# ESC_A.net
KiCad netlist of a schematic drawn in Altium Designer
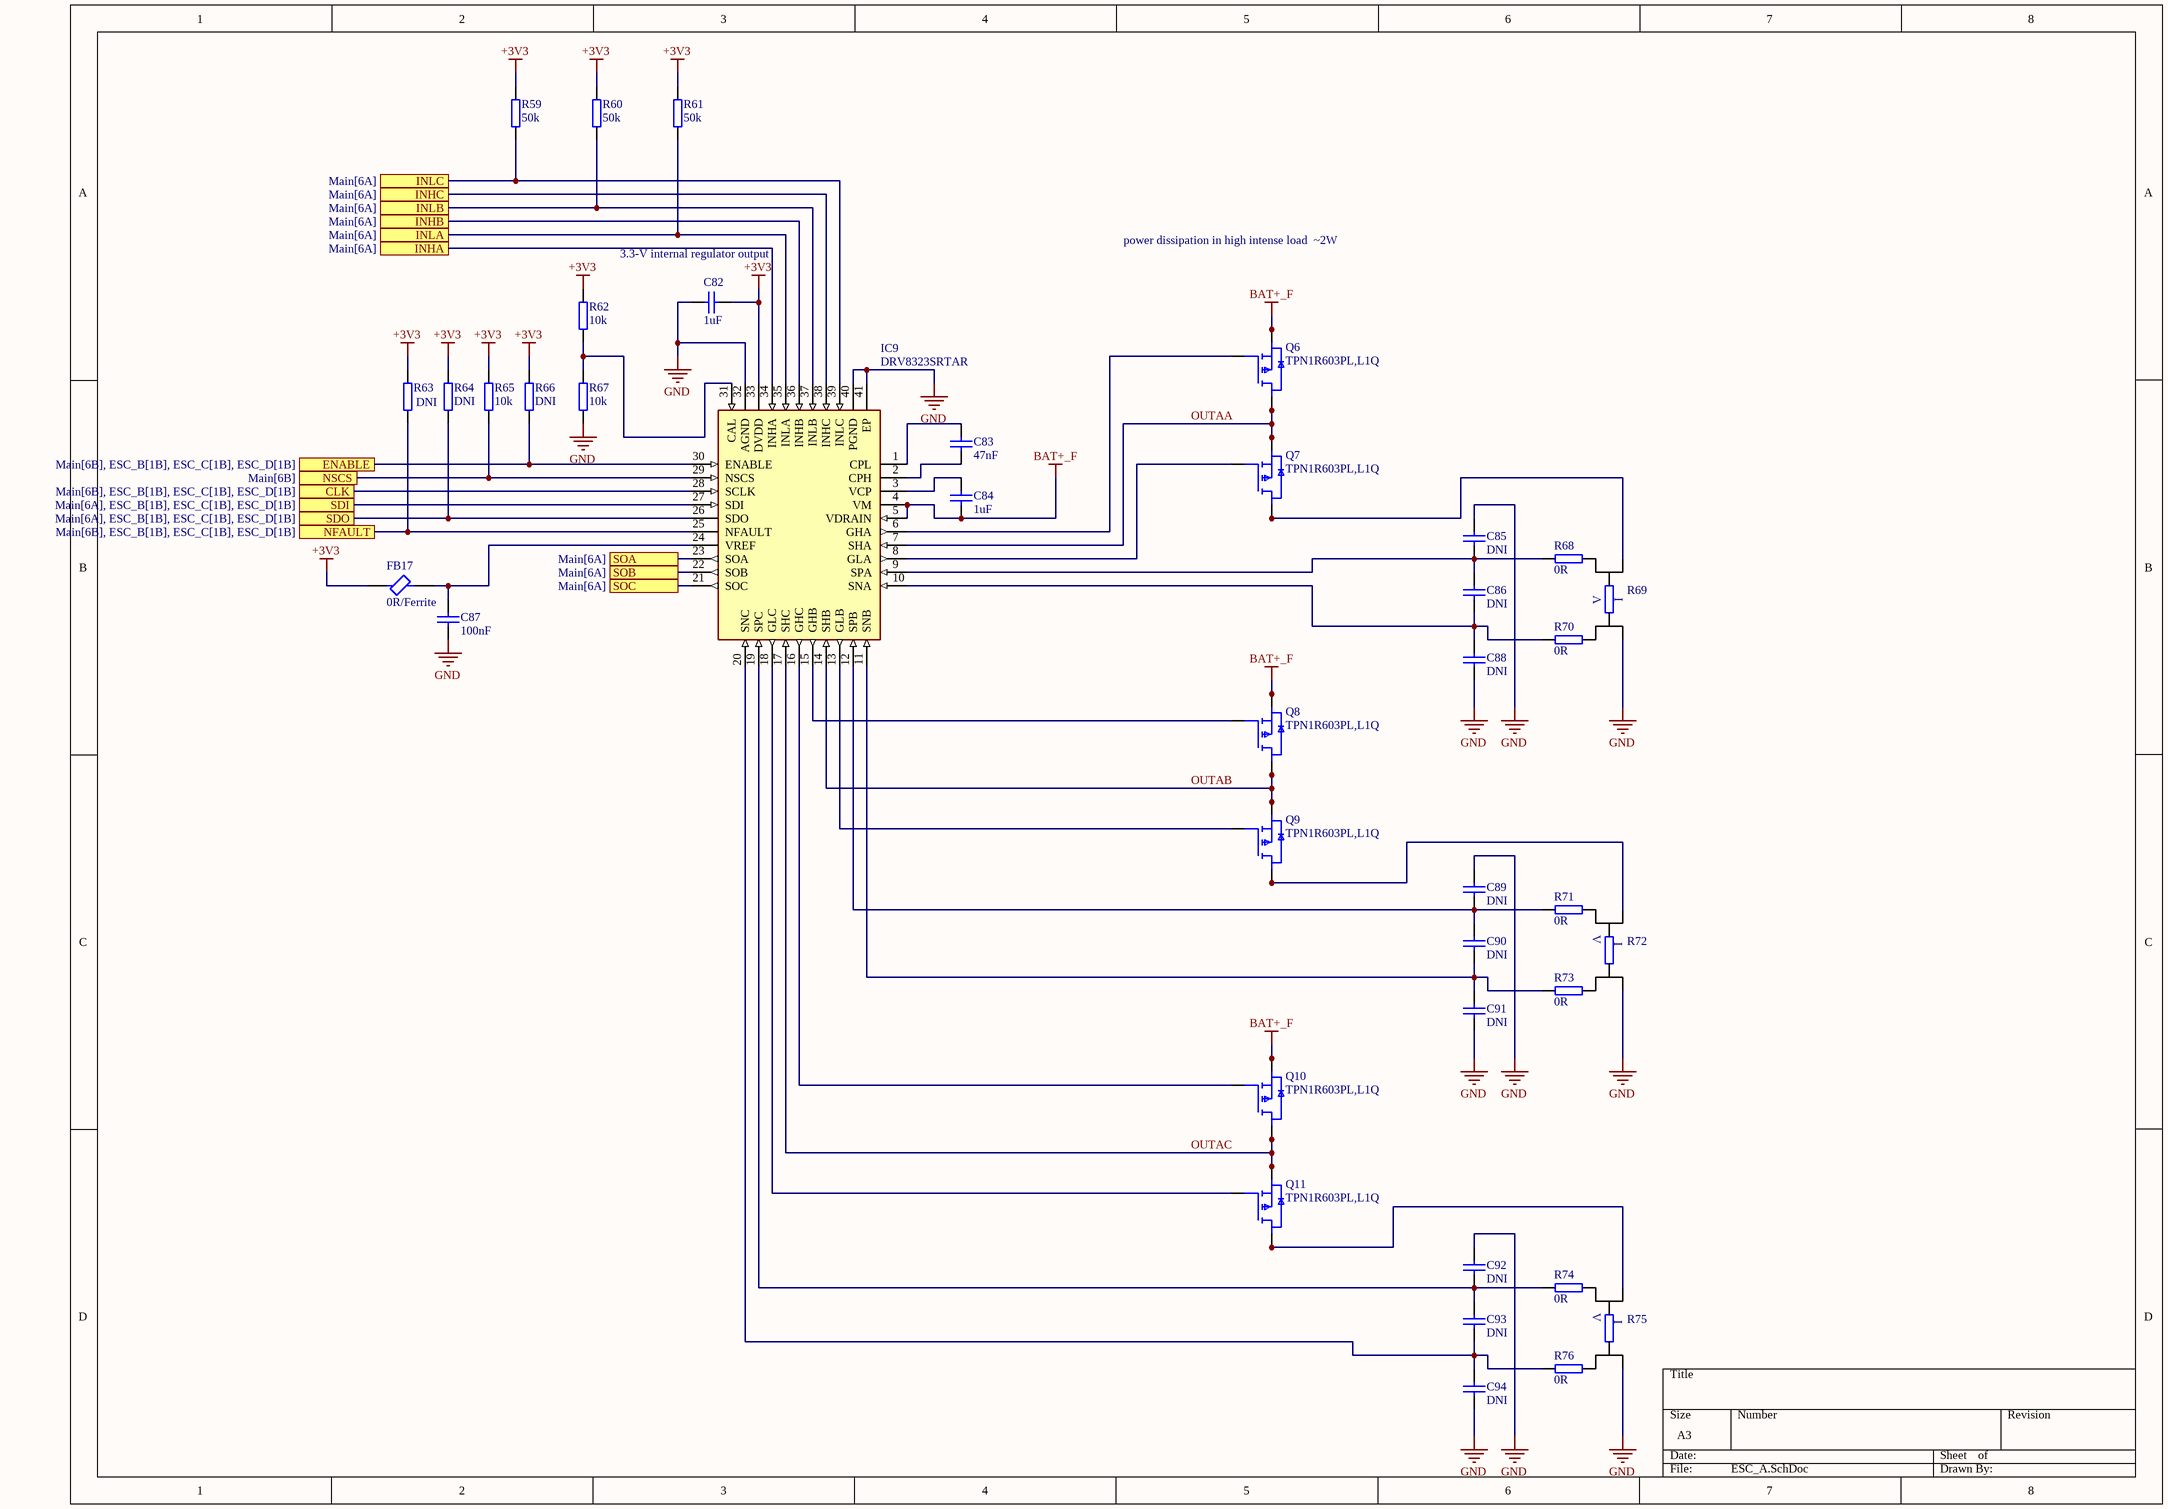
[diagram p0: ESC_A.SchDoc]

(export (version "E")
  (design (tool "Eeschema 10.0.6"))
  (components
    (comp (ref "C82")
      (value "1uF")
      (footprint "CAP0402")
      (fields (field (name "VOLTAGE") "val") (field (name "Comment") "Cap0402"))
      (libsource (lib "capacitorsSMD") (part "Cap0402"))
    )
    (comp (ref "C83")
      (value "47nF")
      (footprint "CAP0603")
      (description "50V")
      (fields (field (name "Comment") "CapSMD0603") (field (name "PUBLISHER") "Altium Limited"))
      (libsource (lib "capacitorsSMD") (part "CapSMD0603"))
    )
    (comp (ref "C84")
      (value "1uF")
      (footprint "CAP0603")
      (description "50V")
      (fields (field (name "Comment") "CapSMD0603") (field (name "PUBLISHER") "Altium Limited"))
      (libsource (lib "capacitorsSMD") (part "CapSMD0603"))
    )
    (comp (ref "C85")
      (value "DNI")
      (footprint "CAP0402")
      (fields (field (name "Comment") "Cap0402"))
      (libsource (lib "capacitorsSMD") (part "Cap0402"))
    )
    (comp (ref "C86")
      (value "DNI")
      (footprint "CAP0402")
      (fields (field (name "Comment") "Cap0402"))
      (libsource (lib "capacitorsSMD") (part "Cap0402"))
    )
    (comp (ref "C87")
      (value "100nF")
      (footprint "CAP0402")
      (fields (field (name "VOLTAGE") "6V3") (field (name "Comment") "Cap0402"))
      (libsource (lib "capacitorsSMD") (part "Cap0402"))
    )
    (comp (ref "C88")
      (value "DNI")
      (footprint "CAP0402")
      (fields (field (name "Comment") "Cap0402"))
      (libsource (lib "capacitorsSMD") (part "Cap0402"))
    )
    (comp (ref "C89")
      (value "DNI")
      (footprint "CAP0402")
      (fields (field (name "Comment") "Cap0402"))
      (libsource (lib "capacitorsSMD") (part "Cap0402"))
    )
    (comp (ref "C90")
      (value "DNI")
      (footprint "CAP0402")
      (fields (field (name "Comment") "Cap0402"))
      (libsource (lib "capacitorsSMD") (part "Cap0402"))
    )
    (comp (ref "C91")
      (value "DNI")
      (footprint "CAP0402")
      (fields (field (name "Comment") "Cap0402"))
      (libsource (lib "capacitorsSMD") (part "Cap0402"))
    )
    (comp (ref "C92")
      (value "DNI")
      (footprint "CAP0402")
      (fields (field (name "Comment") "Cap0402"))
      (libsource (lib "capacitorsSMD") (part "Cap0402"))
    )
    (comp (ref "C93")
      (value "DNI")
      (footprint "CAP0402")
      (fields (field (name "Comment") "Cap0402"))
      (libsource (lib "capacitorsSMD") (part "Cap0402"))
    )
    (comp (ref "C94")
      (value "DNI")
      (footprint "CAP0402")
      (fields (field (name "Comment") "Cap0402"))
      (libsource (lib "capacitorsSMD") (part "Cap0402"))
    )
    (comp (ref "FB17")
      (value "0R/Ferrite")
      (footprint "SamacSys:NFZ15SG152SN10B")
      (description "Ferrite Bead")
      (fields
        (field (name "MANUFACTURER_PART_NUMBER") "BLM15PE471SH1D")
        (field (name "MOUSER PART NUMBER") "81-BLM15PE471SH1D")
      )
      (libsource (lib "SamacSys") (part "BLM15PE471SH1D"))
    )
    (comp (ref "IC9")
      (value "DRV8323SRTAR")
      (footprint "SamacSys:QFN50P600X600X80-41N-D")
      (description "Integrated Circuit")
      (fields (field (name "MOUSER PART NUMBER") "595-DRV8323SRTAR"))
      (libsource (lib "*") (part "DRV8323SRTAR"))
    )
    (comp (ref "Q6")
      (value "TPN1R603PL,L1Q")
      (footprint "SamacSys:TPN1R603PLL1Q")
      (description "MOSFET (N-Channel)")
      (fields (field (name "MOUSER PART NUMBER") "757-TPN1R603PLL1Q"))
      (libsource (lib "SamacSys") (part "TPN1R603PL,L1Q"))
    )
    (comp (ref "Q7")
      (value "TPN1R603PL,L1Q")
      (footprint "SamacSys:TPN1R603PLL1Q")
      (description "MOSFET (N-Channel)")
      (fields (field (name "MOUSER PART NUMBER") "757-TPN1R603PLL1Q"))
      (libsource (lib "SamacSys") (part "TPN1R603PL,L1Q"))
    )
    (comp (ref "Q8")
      (value "TPN1R603PL,L1Q")
      (footprint "SamacSys:TPN1R603PLL1Q")
      (description "MOSFET (N-Channel)")
      (fields (field (name "MOUSER PART NUMBER") "757-TPN1R603PLL1Q"))
      (libsource (lib "SamacSys") (part "TPN1R603PL,L1Q"))
    )
    (comp (ref "Q9")
      (value "TPN1R603PL,L1Q")
      (footprint "SamacSys:TPN1R603PLL1Q")
      (description "MOSFET (N-Channel)")
      (fields (field (name "MOUSER PART NUMBER") "757-TPN1R603PLL1Q"))
      (libsource (lib "SamacSys") (part "TPN1R603PL,L1Q"))
    )
    (comp (ref "Q10")
      (value "TPN1R603PL,L1Q")
      (footprint "SamacSys:TPN1R603PLL1Q")
      (description "MOSFET (N-Channel)")
      (fields (field (name "MOUSER PART NUMBER") "757-TPN1R603PLL1Q"))
      (libsource (lib "SamacSys") (part "TPN1R603PL,L1Q"))
    )
    (comp (ref "Q11")
      (value "TPN1R603PL,L1Q")
      (footprint "SamacSys:TPN1R603PLL1Q")
      (description "MOSFET (N-Channel)")
      (fields (field (name "MOUSER PART NUMBER") "757-TPN1R603PLL1Q"))
      (libsource (lib "SamacSys") (part "TPN1R603PL,L1Q"))
    )
    (comp (ref "R59")
      (value "50k")
      (footprint "RES0402")
      (fields (field (name "Comment") "Res0402"))
      (libsource (lib "resistorSMD") (part "Res0402"))
    )
    (comp (ref "R60")
      (value "50k")
      (footprint "RES0402")
      (fields (field (name "Comment") "Res0402"))
      (libsource (lib "resistorSMD") (part "Res0402"))
    )
    (comp (ref "R61")
      (value "50k")
      (footprint "RES0402")
      (fields (field (name "Comment") "Res0402"))
      (libsource (lib "resistorSMD") (part "Res0402"))
    )
    (comp (ref "R62")
      (value "10k")
      (footprint "RES0402")
      (fields (field (name "Comment") "Res0402"))
      (libsource (lib "resistorSMD") (part "Res0402"))
    )
    (comp (ref "R63")
      (value "DNI")
      (footprint "RES0402")
      (fields (field (name "Comment") "Res0402"))
      (libsource (lib "resistorSMD") (part "Res0402"))
    )
    (comp (ref "R64")
      (value "DNI")
      (footprint "RES0402")
      (fields (field (name "Comment") "Res0402"))
      (libsource (lib "resistorSMD") (part "Res0402"))
    )
    (comp (ref "R65")
      (value "10k")
      (footprint "RES0402")
      (fields (field (name "Comment") "Res0402"))
      (libsource (lib "resistorSMD") (part "Res0402"))
    )
    (comp (ref "R66")
      (value "DNI")
      (footprint "RES0402")
      (fields (field (name "Comment") "Res0402"))
      (libsource (lib "resistorSMD") (part "Res0402"))
    )
    (comp (ref "R67")
      (value "10k")
      (footprint "RES0402")
      (fields (field (name "Comment") "Res0402"))
      (libsource (lib "resistorSMD") (part "Res0402"))
    )
    (comp (ref "R68")
      (value "0R")
      (footprint "RES0402")
      (fields (field (name "Comment") "Res0402"))
      (libsource (lib "resistorSMD") (part "Res0402"))
    )
    (comp (ref "R69")
      (value "WSK12161L000FEA")
      (footprint "SamacSys:WSK12161L000FEA")
      (description "Resistor")
      (fields
        (field (name "MANUFACTURER_PART_NUMBER") "WSK1216L5000FEA")
        (field (name "MOUSER PART NUMBER") "71-WSK1216L5000FEA")
      )
      (libsource (lib "SamacSys") (part "WSK1216L5000FEA"))
    )
    (comp (ref "R70")
      (value "0R")
      (footprint "RES0402")
      (fields (field (name "Comment") "Res0402"))
      (libsource (lib "resistorSMD") (part "Res0402"))
    )
    (comp (ref "R71")
      (value "0R")
      (footprint "RES0402")
      (fields (field (name "Comment") "Res0402"))
      (libsource (lib "resistorSMD") (part "Res0402"))
    )
    (comp (ref "R72")
      (value "WSK12161L000FEA")
      (footprint "SamacSys:WSK12161L000FEA")
      (description "Resistor")
      (fields
        (field (name "MANUFACTURER_PART_NUMBER") "WSK1216L5000FEA")
        (field (name "MOUSER PART NUMBER") "71-WSK1216L5000FEA")
      )
      (libsource (lib "SamacSys") (part "WSK1216L5000FEA"))
    )
    (comp (ref "R73")
      (value "0R")
      (footprint "RES0402")
      (fields (field (name "Comment") "Res0402"))
      (libsource (lib "resistorSMD") (part "Res0402"))
    )
    (comp (ref "R74")
      (value "0R")
      (footprint "RES0402")
      (fields (field (name "Comment") "Res0402"))
      (libsource (lib "resistorSMD") (part "Res0402"))
    )
    (comp (ref "R75")
      (value "WSK12161L000FEA")
      (footprint "SamacSys:WSK12161L000FEA")
      (description "Resistor")
      (fields
        (field (name "MANUFACTURER_PART_NUMBER") "WSK1216L5000FEA")
        (field (name "MOUSER PART NUMBER") "71-WSK1216L5000FEA")
      )
      (libsource (lib "SamacSys") (part "WSK1216L5000FEA"))
    )
    (comp (ref "R76")
      (value "0R")
      (footprint "RES0402")
      (fields (field (name "Comment") "Res0402"))
      (libsource (lib "resistorSMD") (part "Res0402"))
    )
  )
  (nets
    (net (code "1") (name "+3V3") (class "Default")
      (node (ref "C82") (pin "2") (pinfunction "2_2") (pintype "passive"))
      (node (ref "FB17") (pin "1") (pinfunction "1_1") (pintype "passive"))
      (node (ref "IC9") (pin "33") (pinfunction "DVDD_33") (pintype "power_in"))
      (node (ref "R59") (pin "2") (pinfunction "2_2") (pintype "passive"))
      (node (ref "R60") (pin "2") (pinfunction "2_2") (pintype "passive"))
      (node (ref "R61") (pin "2") (pinfunction "2_2") (pintype "passive"))
      (node (ref "R62") (pin "2") (pinfunction "2_2") (pintype "passive"))
      (node (ref "R63") (pin "2") (pinfunction "2_2") (pintype "passive"))
      (node (ref "R64") (pin "2") (pinfunction "2_2") (pintype "passive"))
      (node (ref "R65") (pin "2") (pinfunction "2_2") (pintype "passive"))
      (node (ref "R66") (pin "2") (pinfunction "2_2") (pintype "passive"))
    )
    (net (code "2") (name "/CLK") (class "Default")
      (node (ref "IC9") (pin "28") (pinfunction "SCLK_28") (pintype "input"))
    )
    (net (code "3") (name "/ENABLE") (class "Default")
      (node (ref "IC9") (pin "30") (pinfunction "ENABLE_30") (pintype "input"))
      (node (ref "R66") (pin "1") (pinfunction "1_1") (pintype "passive"))
    )
    (net (code "4") (name "/INHA") (class "Default")
      (node (ref "IC9") (pin "34") (pinfunction "INHA_34") (pintype "input"))
    )
    (net (code "5") (name "/INHB") (class "Default")
      (node (ref "IC9") (pin "36") (pinfunction "INHB_36") (pintype "input"))
    )
    (net (code "6") (name "/INHC") (class "Default")
      (node (ref "IC9") (pin "38") (pinfunction "INHC_38") (pintype "input"))
    )
    (net (code "7") (name "/INLA") (class "Default")
      (node (ref "IC9") (pin "35") (pinfunction "INLA_35") (pintype "input"))
      (node (ref "R61") (pin "1") (pinfunction "1_1") (pintype "passive"))
    )
    (net (code "8") (name "/INLB") (class "Default")
      (node (ref "IC9") (pin "37") (pinfunction "INLB_37") (pintype "input"))
      (node (ref "R60") (pin "1") (pinfunction "1_1") (pintype "passive"))
    )
    (net (code "9") (name "/INLC") (class "Default")
      (node (ref "IC9") (pin "39") (pinfunction "INLC_39") (pintype "input"))
      (node (ref "R59") (pin "1") (pinfunction "1_1") (pintype "passive"))
    )
    (net (code "10") (name "/NFAULT") (class "Default")
      (node (ref "IC9") (pin "25") (pinfunction "NFAULT_25") (pintype "passive"))
      (node (ref "R63") (pin "1") (pinfunction "1_1") (pintype "passive"))
    )
    (net (code "11") (name "/NSCS") (class "Default")
      (node (ref "IC9") (pin "29") (pinfunction "NSCS_29") (pintype "input"))
      (node (ref "R65") (pin "1") (pinfunction "1_1") (pintype "passive"))
    )
    (net (code "12") (name "/OUTAA") (class "Default")
      (node (ref "IC9") (pin "7") (pinfunction "SHA_7") (pintype "input"))
      (node (ref "Q6") (pin "5") (pinfunction "D_1_5") (pintype "passive"))
      (node (ref "Q6") (pin "6") (pinfunction "D_2_6") (pintype "passive"))
      (node (ref "Q6") (pin "7") (pinfunction "D_3_7") (pintype "passive"))
      (node (ref "Q6") (pin "8") (pinfunction "D_4_8") (pintype "passive"))
      (node (ref "Q6") (pin "9") (pinfunction "D_4_9") (pintype "passive"))
      (node (ref "Q7") (pin "1") (pinfunction "S_1_1") (pintype "passive"))
      (node (ref "Q7") (pin "2") (pinfunction "S_2_2") (pintype "passive"))
      (node (ref "Q7") (pin "3") (pinfunction "S_3_3") (pintype "passive"))
    )
    (net (code "13") (name "/OUTAB") (class "Default")
      (node (ref "IC9") (pin "14") (pinfunction "SHB_14") (pintype "input"))
      (node (ref "Q8") (pin "5") (pinfunction "D_1_5") (pintype "passive"))
      (node (ref "Q8") (pin "6") (pinfunction "D_2_6") (pintype "passive"))
      (node (ref "Q8") (pin "7") (pinfunction "D_3_7") (pintype "passive"))
      (node (ref "Q8") (pin "8") (pinfunction "D_4_8") (pintype "passive"))
      (node (ref "Q8") (pin "9") (pinfunction "D_4_9") (pintype "passive"))
      (node (ref "Q9") (pin "1") (pinfunction "S_1_1") (pintype "passive"))
      (node (ref "Q9") (pin "2") (pinfunction "S_2_2") (pintype "passive"))
      (node (ref "Q9") (pin "3") (pinfunction "S_3_3") (pintype "passive"))
    )
    (net (code "14") (name "/OUTAC") (class "Default")
      (node (ref "IC9") (pin "17") (pinfunction "SHC_17") (pintype "input"))
      (node (ref "Q10") (pin "5") (pinfunction "D_1_5") (pintype "passive"))
      (node (ref "Q10") (pin "6") (pinfunction "D_2_6") (pintype "passive"))
      (node (ref "Q10") (pin "7") (pinfunction "D_3_7") (pintype "passive"))
      (node (ref "Q10") (pin "8") (pinfunction "D_4_8") (pintype "passive"))
      (node (ref "Q10") (pin "9") (pinfunction "D_4_9") (pintype "passive"))
      (node (ref "Q11") (pin "1") (pinfunction "S_1_1") (pintype "passive"))
      (node (ref "Q11") (pin "2") (pinfunction "S_2_2") (pintype "passive"))
      (node (ref "Q11") (pin "3") (pinfunction "S_3_3") (pintype "passive"))
    )
    (net (code "15") (name "/SDI") (class "Default")
      (node (ref "IC9") (pin "27") (pinfunction "SDI_27") (pintype "input"))
    )
    (net (code "16") (name "/SDO") (class "Default")
      (node (ref "IC9") (pin "26") (pinfunction "SDO_26") (pintype "passive"))
      (node (ref "R64") (pin "1") (pinfunction "1_1") (pintype "passive"))
    )
    (net (code "17") (name "/SOA") (class "Default")
      (node (ref "IC9") (pin "23") (pinfunction "SOA_23") (pintype "output"))
    )
    (net (code "18") (name "/SOB") (class "Default")
      (node (ref "IC9") (pin "22") (pinfunction "SOB_22") (pintype "output"))
    )
    (net (code "19") (name "/SOC") (class "Default")
      (node (ref "IC9") (pin "21") (pinfunction "SOC_21") (pintype "output"))
    )
    (net (code "20") (name "BAT+_F") (class "Default")
      (node (ref "C84") (pin "1") (pinfunction "1_1") (pintype "passive"))
      (node (ref "IC9") (pin "4") (pinfunction "VM_4") (pintype "power_in"))
      (node (ref "IC9") (pin "5") (pinfunction "VDRAIN_5") (pintype "input"))
      (node (ref "Q10") (pin "1") (pinfunction "S_1_1") (pintype "passive"))
      (node (ref "Q10") (pin "2") (pinfunction "S_2_2") (pintype "passive"))
      (node (ref "Q10") (pin "3") (pinfunction "S_3_3") (pintype "passive"))
      (node (ref "Q6") (pin "1") (pinfunction "S_1_1") (pintype "passive"))
      (node (ref "Q6") (pin "2") (pinfunction "S_2_2") (pintype "passive"))
      (node (ref "Q6") (pin "3") (pinfunction "S_3_3") (pintype "passive"))
      (node (ref "Q8") (pin "1") (pinfunction "S_1_1") (pintype "passive"))
      (node (ref "Q8") (pin "2") (pinfunction "S_2_2") (pintype "passive"))
      (node (ref "Q8") (pin "3") (pinfunction "S_3_3") (pintype "passive"))
    )
    (net (code "21") (name "GND") (class "Default")
      (node (ref "C82") (pin "1") (pinfunction "1_1") (pintype "passive"))
      (node (ref "C85") (pin "1") (pinfunction "1_1") (pintype "passive"))
      (node (ref "C87") (pin "1") (pinfunction "1_1") (pintype "passive"))
      (node (ref "C88") (pin "2") (pinfunction "2_2") (pintype "passive"))
      (node (ref "C89") (pin "1") (pinfunction "1_1") (pintype "passive"))
      (node (ref "C91") (pin "2") (pinfunction "2_2") (pintype "passive"))
      (node (ref "C92") (pin "1") (pinfunction "1_1") (pintype "passive"))
      (node (ref "C94") (pin "2") (pinfunction "2_2") (pintype "passive"))
      (node (ref "IC9") (pin "32") (pinfunction "AGND_32") (pintype "power_in"))
      (node (ref "IC9") (pin "40") (pinfunction "PGND_40") (pintype "power_in"))
      (node (ref "IC9") (pin "41") (pinfunction "EP_41") (pintype "power_in"))
      (node (ref "R67") (pin "1") (pinfunction "1_1") (pintype "passive"))
      (node (ref "R69") (pin "1") (pinfunction "1_1") (pintype "passive"))
      (node (ref "R72") (pin "4") (pinfunction "4_4") (pintype "passive"))
      (node (ref "R75") (pin "4") (pinfunction "4_4") (pintype "passive"))
    )
    (net (code "22") (name "Net-(IC9-CAL)") (class "Default")
      (node (ref "IC9") (pin "31") (pinfunction "CAL_31") (pintype "input"))
      (node (ref "R62") (pin "1") (pinfunction "1_1") (pintype "passive"))
      (node (ref "R67") (pin "2") (pinfunction "2_2") (pintype "passive"))
    )
    (net (code "23") (name "Net-(IC9-CPH)") (class "Default")
      (node (ref "C83") (pin "1") (pinfunction "1_1") (pintype "passive"))
      (node (ref "IC9") (pin "2") (pinfunction "CPH_2") (pintype "power_in"))
    )
    (net (code "24") (name "Net-(IC9-CPL)") (class "Default")
      (node (ref "C83") (pin "2") (pinfunction "2_2") (pintype "passive"))
      (node (ref "IC9") (pin "1") (pinfunction "CPL_1") (pintype "power_in"))
    )
    (net (code "25") (name "Net-(IC9-GHA)") (class "Default")
      (node (ref "IC9") (pin "6") (pinfunction "GHA_6") (pintype "output"))
      (node (ref "Q6") (pin "4") (pinfunction "G_4") (pintype "passive"))
    )
    (net (code "26") (name "Net-(IC9-GHB)") (class "Default")
      (node (ref "IC9") (pin "15") (pinfunction "GHB_15") (pintype "output"))
      (node (ref "Q8") (pin "4") (pinfunction "G_4") (pintype "passive"))
    )
    (net (code "27") (name "Net-(IC9-GHC)") (class "Default")
      (node (ref "IC9") (pin "16") (pinfunction "GHC_16") (pintype "output"))
      (node (ref "Q10") (pin "4") (pinfunction "G_4") (pintype "passive"))
    )
    (net (code "28") (name "Net-(IC9-GLA)") (class "Default")
      (node (ref "IC9") (pin "8") (pinfunction "GLA_8") (pintype "output"))
      (node (ref "Q7") (pin "4") (pinfunction "G_4") (pintype "passive"))
    )
    (net (code "29") (name "Net-(IC9-GLB)") (class "Default")
      (node (ref "IC9") (pin "13") (pinfunction "GLB_13") (pintype "output"))
      (node (ref "Q9") (pin "4") (pinfunction "G_4") (pintype "passive"))
    )
    (net (code "30") (name "Net-(IC9-GLC)") (class "Default")
      (node (ref "IC9") (pin "18") (pinfunction "GLC_18") (pintype "output"))
      (node (ref "Q11") (pin "4") (pinfunction "G_4") (pintype "passive"))
    )
    (net (code "31") (name "Net-(IC9-SNA)") (class "Default")
      (node (ref "C86") (pin "2") (pinfunction "2_2") (pintype "passive"))
      (node (ref "C88") (pin "1") (pinfunction "1_1") (pintype "passive"))
      (node (ref "IC9") (pin "10") (pinfunction "SNA_10") (pintype "input"))
      (node (ref "R70") (pin "1") (pinfunction "1_1") (pintype "passive"))
    )
    (net (code "32") (name "Net-(IC9-SNB)") (class "Default")
      (node (ref "C90") (pin "2") (pinfunction "2_2") (pintype "passive"))
      (node (ref "C91") (pin "1") (pinfunction "1_1") (pintype "passive"))
      (node (ref "IC9") (pin "11") (pinfunction "SNB_11") (pintype "input"))
      (node (ref "R73") (pin "1") (pinfunction "1_1") (pintype "passive"))
    )
    (net (code "33") (name "Net-(IC9-SNC)") (class "Default")
      (node (ref "C93") (pin "2") (pinfunction "2_2") (pintype "passive"))
      (node (ref "C94") (pin "1") (pinfunction "1_1") (pintype "passive"))
      (node (ref "IC9") (pin "20") (pinfunction "SNC_20") (pintype "input"))
      (node (ref "R76") (pin "1") (pinfunction "1_1") (pintype "passive"))
    )
    (net (code "34") (name "Net-(IC9-SPA)") (class "Default")
      (node (ref "C85") (pin "2") (pinfunction "2_2") (pintype "passive"))
      (node (ref "C86") (pin "1") (pinfunction "1_1") (pintype "passive"))
      (node (ref "IC9") (pin "9") (pinfunction "SPA_9") (pintype "input"))
      (node (ref "R68") (pin "1") (pinfunction "1_1") (pintype "passive"))
    )
    (net (code "35") (name "Net-(IC9-SPB)") (class "Default")
      (node (ref "C89") (pin "2") (pinfunction "2_2") (pintype "passive"))
      (node (ref "C90") (pin "1") (pinfunction "1_1") (pintype "passive"))
      (node (ref "IC9") (pin "12") (pinfunction "SPB_12") (pintype "input"))
      (node (ref "R71") (pin "1") (pinfunction "1_1") (pintype "passive"))
    )
    (net (code "36") (name "Net-(IC9-SPC)") (class "Default")
      (node (ref "C92") (pin "2") (pinfunction "2_2") (pintype "passive"))
      (node (ref "C93") (pin "1") (pinfunction "1_1") (pintype "passive"))
      (node (ref "IC9") (pin "19") (pinfunction "SPC_19") (pintype "input"))
      (node (ref "R74") (pin "1") (pinfunction "1_1") (pintype "passive"))
    )
    (net (code "37") (name "Net-(IC9-VCP)") (class "Default")
      (node (ref "C84") (pin "2") (pinfunction "2_2") (pintype "passive"))
      (node (ref "IC9") (pin "3") (pinfunction "VCP_3") (pintype "power_in"))
    )
    (net (code "38") (name "Net-(IC9-VREF)") (class "Default")
      (node (ref "C87") (pin "2") (pinfunction "2_2") (pintype "passive"))
      (node (ref "FB17") (pin "2") (pinfunction "2_2") (pintype "passive"))
      (node (ref "IC9") (pin "24") (pinfunction "VREF_24") (pintype "power_in"))
    )
    (net (code "39") (name "Net-(Q7-D_1)") (class "Default")
      (node (ref "Q7") (pin "5") (pinfunction "D_1_5") (pintype "passive"))
      (node (ref "Q7") (pin "6") (pinfunction "D_2_6") (pintype "passive"))
      (node (ref "Q7") (pin "7") (pinfunction "D_3_7") (pintype "passive"))
      (node (ref "Q7") (pin "8") (pinfunction "D_4_8") (pintype "passive"))
      (node (ref "Q7") (pin "9") (pinfunction "D_4_9") (pintype "passive"))
      (node (ref "R69") (pin "4") (pinfunction "4_4") (pintype "passive"))
    )
    (net (code "40") (name "Net-(Q9-D_1)") (class "Default")
      (node (ref "Q9") (pin "5") (pinfunction "D_1_5") (pintype "passive"))
      (node (ref "Q9") (pin "6") (pinfunction "D_2_6") (pintype "passive"))
      (node (ref "Q9") (pin "7") (pinfunction "D_3_7") (pintype "passive"))
      (node (ref "Q9") (pin "8") (pinfunction "D_4_8") (pintype "passive"))
      (node (ref "Q9") (pin "9") (pinfunction "D_4_9") (pintype "passive"))
      (node (ref "R72") (pin "1") (pinfunction "1_1") (pintype "passive"))
    )
    (net (code "41") (name "Net-(Q11-D_1)") (class "Default")
      (node (ref "Q11") (pin "5") (pinfunction "D_1_5") (pintype "passive"))
      (node (ref "Q11") (pin "6") (pinfunction "D_2_6") (pintype "passive"))
      (node (ref "Q11") (pin "7") (pinfunction "D_3_7") (pintype "passive"))
      (node (ref "Q11") (pin "8") (pinfunction "D_4_8") (pintype "passive"))
      (node (ref "Q11") (pin "9") (pinfunction "D_4_9") (pintype "passive"))
      (node (ref "R75") (pin "1") (pinfunction "1_1") (pintype "passive"))
    )
    (net (code "42") (name "Net-(R68-Pad2)") (class "Default")
      (node (ref "R68") (pin "2") (pinfunction "2_2") (pintype "passive"))
      (node (ref "R69") (pin "3") (pinfunction "3_3") (pintype "passive"))
    )
    (net (code "43") (name "Net-(R69-Pad2)") (class "Default")
      (node (ref "R69") (pin "2") (pinfunction "2_2") (pintype "passive"))
      (node (ref "R70") (pin "2") (pinfunction "2_2") (pintype "passive"))
    )
    (net (code "44") (name "Net-(R71-Pad2)") (class "Default")
      (node (ref "R71") (pin "2") (pinfunction "2_2") (pintype "passive"))
      (node (ref "R72") (pin "2") (pinfunction "2_2") (pintype "passive"))
    )
    (net (code "45") (name "Net-(R72-Pad3)") (class "Default")
      (node (ref "R72") (pin "3") (pinfunction "3_3") (pintype "passive"))
      (node (ref "R73") (pin "2") (pinfunction "2_2") (pintype "passive"))
    )
    (net (code "46") (name "Net-(R74-Pad2)") (class "Default")
      (node (ref "R74") (pin "2") (pinfunction "2_2") (pintype "passive"))
      (node (ref "R75") (pin "2") (pinfunction "2_2") (pintype "passive"))
    )
    (net (code "47") (name "Net-(R75-Pad3)") (class "Default")
      (node (ref "R75") (pin "3") (pinfunction "3_3") (pintype "passive"))
      (node (ref "R76") (pin "2") (pinfunction "2_2") (pintype "passive"))
    )
  )
)
